# untitled.net
KiCad netlist of a schematic drawn in EAGLE
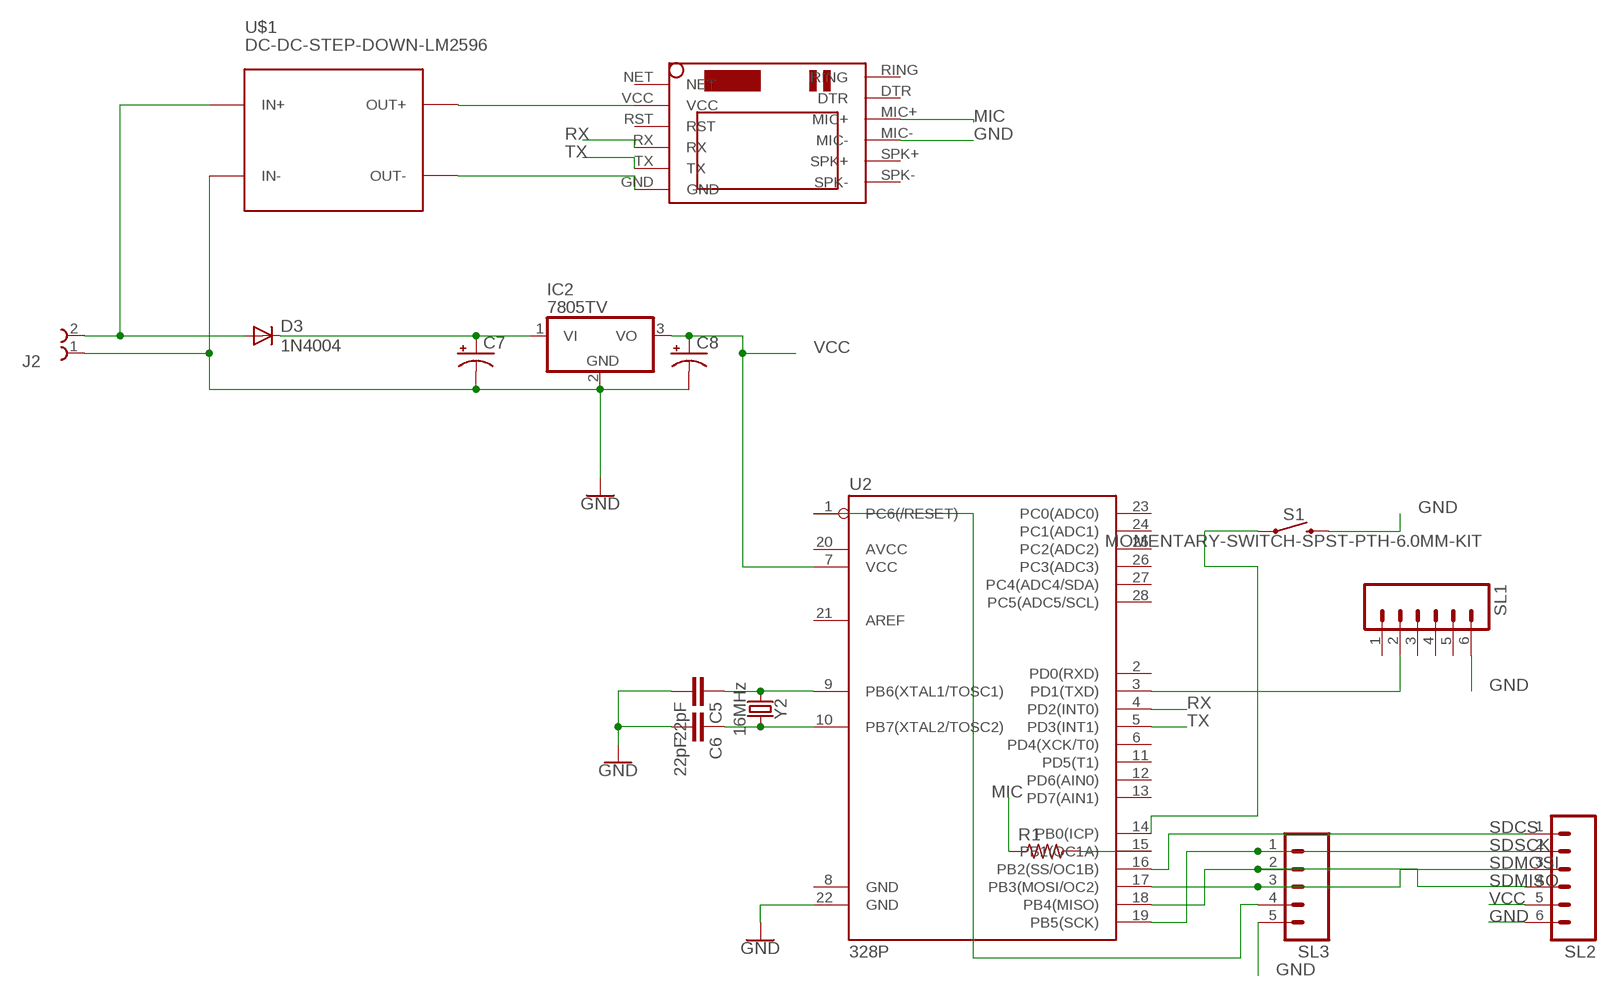
[diagram p0: schematic, sheet 1]

(export (version "E")
  (design (tool "Eeschema 10.0.6"))
  (components
    (comp (ref "C5")
      (value "22pF")
      (footprint "eagle-import:CAP-PTH-2.54")
      (libsource (lib "eagle-import") (part "22PF-PTH-2.54MM-200V-5%"))
    )
    (comp (ref "C6")
      (value "22pF")
      (footprint "eagle-import:CAP-PTH-2.54")
      (libsource (lib "eagle-import") (part "22PF-PTH-2.54MM-200V-5%"))
    )
    (comp (ref "C7")
      (value "CAPACITOR-PE5-8.5")
      (footprint "eagle-import:E5-8,5")
      (libsource (lib "eagle-import") (part "CAPACITOR-PE5-8.5"))
    )
    (comp (ref "C8")
      (value "CAPACITOR-PE5-5")
      (footprint "eagle-import:E5-5")
      (libsource (lib "eagle-import") (part "CAPACITOR-PE5-5"))
    )
    (comp (ref "D3")
      (value "1N4004")
      (footprint "eagle-import:DO41-10")
      (libsource (lib "eagle-import") (part "1N4004"))
    )
    (comp (ref "IC2")
      (value "7805TV")
      (footprint "eagle-import:TO220V")
      (libsource (lib "eagle-import") (part "78TV05"))
    )
    (comp (ref "J2")
      (value "691201520002")
      (footprint "eagle-import:691201520002")
      (libsource (lib "eagle-import") (part "691201520002"))
    )
    (comp (ref "R1")
      (value "R-US_0207/10")
      (footprint "eagle-import:0207_10")
      (libsource (lib "eagle-import") (part "R-US_0207/10"))
    )
    (comp (ref "S1")
      (value "MOMENTARY-SWITCH-SPST-PTH-6.0MM-KIT")
      (footprint "eagle-import:TACTILE_SWITCH_PTH_6.0MM_KIT")
      (libsource (lib "eagle-import") (part "MOMENTARY-SWITCH-SPST-PTH-6.0MM-KIT"))
    )
    (comp (ref "SL1")
      (value "M06")
      (footprint "eagle-import:06P")
      (libsource (lib "eagle-import") (part "M06"))
    )
    (comp (ref "SL2")
      (value "M06")
      (footprint "eagle-import:06P")
      (libsource (lib "eagle-import") (part "M06"))
    )
    (comp (ref "SL3")
      (value "M05")
      (footprint "eagle-import:05P")
      (libsource (lib "eagle-import") (part "M05"))
    )
    (comp (ref "U$1")
      (value "DC-DC-STEP-DOWN-LM2596")
      (footprint "eagle-import:DC-DC-STEP-DOWN-LM2596")
      (libsource (lib "eagle-import") (part "DC-DC-STEP-DOWN-LM2596"))
    )
    (comp (ref "U$2")
      (value "SIM800LMODULE")
      (footprint "eagle-import:SIM800LMODULE")
      (libsource (lib "eagle-import") (part "SIM800LMODULE"))
    )
    (comp (ref "U2")
      (value "328P")
      (footprint "eagle-import:DIP28")
      (libsource (lib "eagle-import") (part "ATMEGA328P_PDIP"))
    )
    (comp (ref "Y2")
      (value "16MHz")
      (footprint "eagle-import:HC49US")
      (libsource (lib "eagle-import") (part "CRYSTAL-16MHZPTH-HC49US"))
    )
  )
  (nets
    (net (code "1") (name "/MIC") (class "Default")
      (node (ref "R1") (pin "1") (pinfunction "1_1") (pintype "passive"))
      (node (ref "U$2") (pin "MIC+") (pinfunction "MIC+_MIC+") (pintype "bidirectional"))
    )
    (net (code "2") (name "/RX") (class "Default")
      (node (ref "U$2") (pin "RX") (pinfunction "RX_RX") (pintype "bidirectional"))
      (node (ref "U2") (pin "4") (pinfunction "PD2(INT0)_4") (pintype "bidirectional"))
    )
    (net (code "3") (name "/SDCS") (class "Default")
      (node (ref "SL2") (pin "1") (pinfunction "1_1") (pintype "passive"))
      (node (ref "U2") (pin "16") (pinfunction "PB2(SS/OC1B)_16") (pintype "bidirectional"))
    )
    (net (code "4") (name "/SDMISO") (class "Default")
      (node (ref "SL2") (pin "4") (pinfunction "4_4") (pintype "passive"))
      (node (ref "SL3") (pin "2") (pinfunction "2_2") (pintype "passive"))
      (node (ref "U2") (pin "18") (pinfunction "PB4(MISO)_18") (pintype "bidirectional"))
    )
    (net (code "5") (name "/SDMOSI") (class "Default")
      (node (ref "SL2") (pin "3") (pinfunction "3_3") (pintype "passive"))
      (node (ref "SL3") (pin "3") (pinfunction "3_3") (pintype "passive"))
      (node (ref "U2") (pin "17") (pinfunction "PB3(MOSI/OC2)_17") (pintype "bidirectional"))
    )
    (net (code "6") (name "/SDSCK") (class "Default")
      (node (ref "SL2") (pin "2") (pinfunction "2_2") (pintype "passive"))
      (node (ref "SL3") (pin "1") (pinfunction "1_1") (pintype "passive"))
      (node (ref "U2") (pin "19") (pinfunction "PB5(SCK)_19") (pintype "bidirectional"))
    )
    (net (code "7") (name "/TX") (class "Default")
      (node (ref "U$2") (pin "TX") (pinfunction "TX_TX") (pintype "bidirectional"))
      (node (ref "U2") (pin "5") (pinfunction "PD3(INT1)_5") (pintype "bidirectional"))
    )
    (net (code "8") (name "/VCC") (class "Default")
      (node (ref "C8") (pin "+") (pinfunction "+_+") (pintype "passive"))
      (node (ref "IC2") (pin "3") (pinfunction "VO_3") (pintype "passive"))
      (node (ref "SL2") (pin "5") (pinfunction "5_5") (pintype "passive"))
      (node (ref "U2") (pin "7") (pinfunction "VCC_7") (pintype "bidirectional"))
    )
    (net (code "9") (name "GND") (class "Default")
      (node (ref "C5") (pin "2") (pinfunction "2_2") (pintype "passive"))
      (node (ref "C6") (pin "2") (pinfunction "2_2") (pintype "passive"))
      (node (ref "C7") (pin "-") (pinfunction "-_-") (pintype "passive"))
      (node (ref "C8") (pin "-") (pinfunction "-_-") (pintype "passive"))
      (node (ref "IC2") (pin "2") (pinfunction "GND_2") (pintype "passive"))
      (node (ref "J2") (pin "1") (pinfunction "1_1") (pintype "passive"))
      (node (ref "S1") (pin "3") (pinfunction "2_3") (pintype "passive"))
      (node (ref "SL1") (pin "6") (pinfunction "6_6") (pintype "passive"))
      (node (ref "SL2") (pin "6") (pinfunction "6_6") (pintype "passive"))
      (node (ref "SL3") (pin "5") (pinfunction "5_5") (pintype "passive"))
      (node (ref "U$1") (pin "IN-") (pinfunction "IN-_IN-") (pintype "bidirectional"))
      (node (ref "U$2") (pin "MIC-") (pinfunction "MIC-_MIC-") (pintype "bidirectional"))
      (node (ref "U2") (pin "22") (pinfunction "GND_22") (pintype "bidirectional"))
    )
    (net (code "10") (name "Net-(D3-PadA)") (class "Default")
      (node (ref "D3") (pin "A") (pinfunction "A_A") (pintype "passive"))
      (node (ref "J2") (pin "2") (pinfunction "2_2") (pintype "passive"))
      (node (ref "U$1") (pin "IN+") (pinfunction "IN+_IN+") (pintype "bidirectional"))
    )
    (net (code "11") (name "Net-(IC2-VI)") (class "Default")
      (node (ref "C7") (pin "+") (pinfunction "+_+") (pintype "passive"))
      (node (ref "D3") (pin "C") (pinfunction "C_C") (pintype "passive"))
      (node (ref "IC2") (pin "1") (pinfunction "VI_1") (pintype "input"))
    )
    (net (code "12") (name "Net-(U$1-PadOUT+)") (class "Default")
      (node (ref "U$1") (pin "OUT+") (pinfunction "OUT+_OUT+") (pintype "bidirectional"))
      (node (ref "U$2") (pin "VCC") (pinfunction "VCC_VCC") (pintype "bidirectional"))
    )
    (net (code "13") (name "Net-(U$1-PadOUT-)") (class "Default")
      (node (ref "U$1") (pin "OUT-") (pinfunction "OUT-_OUT-") (pintype "bidirectional"))
      (node (ref "U$2") (pin "GND") (pinfunction "GND_GND") (pintype "bidirectional"))
    )
    (net (code "14") (name "Net-(U2-PB0(ICP))") (class "Default")
      (node (ref "S1") (pin "1") (pinfunction "1_1") (pintype "passive"))
      (node (ref "U2") (pin "14") (pinfunction "PB0(ICP)_14") (pintype "bidirectional"))
    )
    (net (code "15") (name "Net-(U2-PB1(OC1A))") (class "Default")
      (node (ref "R1") (pin "2") (pinfunction "2_2") (pintype "passive"))
      (node (ref "U2") (pin "15") (pinfunction "PB1(OC1A)_15") (pintype "bidirectional"))
    )
    (net (code "16") (name "Net-(U2-PB6(XTAL1{slash}TOSC1))") (class "Default")
      (node (ref "C5") (pin "1") (pinfunction "1_1") (pintype "passive"))
      (node (ref "U2") (pin "9") (pinfunction "PB6(XTAL1/TOSC1)_9") (pintype "bidirectional"))
      (node (ref "Y2") (pin "1") (pinfunction "1_1") (pintype "passive"))
    )
    (net (code "17") (name "Net-(U2-PB7(XTAL2{slash}TOSC2))") (class "Default")
      (node (ref "C6") (pin "1") (pinfunction "1_1") (pintype "passive"))
      (node (ref "U2") (pin "10") (pinfunction "PB7(XTAL2/TOSC2)_10") (pintype "bidirectional"))
      (node (ref "Y2") (pin "2") (pinfunction "2_2") (pintype "passive"))
    )
    (net (code "18") (name "Net-(U2-PC6({slash}RESET))") (class "Default")
      (node (ref "SL3") (pin "4") (pinfunction "4_4") (pintype "passive"))
      (node (ref "U2") (pin "1") (pinfunction "PC6(/RESET)_1") (pintype "bidirectional"))
    )
    (net (code "19") (name "Net-(U2-PD1(TXD))") (class "Default")
      (node (ref "SL1") (pin "2") (pinfunction "2_2") (pintype "passive"))
      (node (ref "U2") (pin "3") (pinfunction "PD1(TXD)_3") (pintype "bidirectional"))
    )
    (net (code "20") (name "unconnected-(SL1-Pad1)") (class "Default")
      (node (ref "SL1") (pin "1") (pinfunction "1_1") (pintype "passive"))
    )
    (net (code "21") (name "unconnected-(SL1-Pad3)") (class "Default")
      (node (ref "SL1") (pin "3") (pinfunction "3_3") (pintype "passive"))
    )
    (net (code "22") (name "unconnected-(SL1-Pad4)") (class "Default")
      (node (ref "SL1") (pin "4") (pinfunction "4_4") (pintype "passive"))
    )
    (net (code "23") (name "unconnected-(SL1-Pad5)") (class "Default")
      (node (ref "SL1") (pin "5") (pinfunction "5_5") (pintype "passive"))
    )
    (net (code "24") (name "unconnected-(U$2-PadDTR)") (class "Default")
      (node (ref "U$2") (pin "DTR") (pinfunction "DTR_DTR") (pintype "bidirectional"))
    )
    (net (code "25") (name "unconnected-(U$2-PadNET)") (class "Default")
      (node (ref "U$2") (pin "NET") (pinfunction "NET_NET") (pintype "bidirectional"))
    )
    (net (code "26") (name "unconnected-(U$2-PadRING)") (class "Default")
      (node (ref "U$2") (pin "RING") (pinfunction "RING_RING") (pintype "bidirectional"))
    )
    (net (code "27") (name "unconnected-(U$2-PadRST)") (class "Default")
      (node (ref "U$2") (pin "RST") (pinfunction "RST_RST") (pintype "bidirectional"))
    )
    (net (code "28") (name "unconnected-(U$2-PadSPK+)") (class "Default")
      (node (ref "U$2") (pin "SPK+") (pinfunction "SPK+_SPK+") (pintype "bidirectional"))
    )
    (net (code "29") (name "unconnected-(U$2-PadSPK-)") (class "Default")
      (node (ref "U$2") (pin "SPK-") (pinfunction "SPK-_SPK-") (pintype "bidirectional"))
    )
    (net (code "30") (name "unconnected-(U2-AREF-Pad21)") (class "Default")
      (node (ref "U2") (pin "21") (pinfunction "AREF_21") (pintype "bidirectional"))
    )
    (net (code "31") (name "unconnected-(U2-AVCC-Pad20)") (class "Default")
      (node (ref "U2") (pin "20") (pinfunction "AVCC_20") (pintype "bidirectional"))
    )
    (net (code "32") (name "unconnected-(U2-GND-Pad8)") (class "Default")
      (node (ref "U2") (pin "8") (pinfunction "GND_8") (pintype "bidirectional"))
    )
    (net (code "33") (name "unconnected-(U2-PC0(ADC0)-Pad23)") (class "Default")
      (node (ref "U2") (pin "23") (pinfunction "PC0(ADC0)_23") (pintype "bidirectional"))
    )
    (net (code "34") (name "unconnected-(U2-PC1(ADC1)-Pad24)") (class "Default")
      (node (ref "U2") (pin "24") (pinfunction "PC1(ADC1)_24") (pintype "bidirectional"))
    )
    (net (code "35") (name "unconnected-(U2-PC2(ADC2)-Pad25)") (class "Default")
      (node (ref "U2") (pin "25") (pinfunction "PC2(ADC2)_25") (pintype "bidirectional"))
    )
    (net (code "36") (name "unconnected-(U2-PC3(ADC3)-Pad26)") (class "Default")
      (node (ref "U2") (pin "26") (pinfunction "PC3(ADC3)_26") (pintype "bidirectional"))
    )
    (net (code "37") (name "unconnected-(U2-PC4(ADC4{slash}SDA)-Pad27)") (class "Default")
      (node (ref "U2") (pin "27") (pinfunction "PC4(ADC4/SDA)_27") (pintype "bidirectional"))
    )
    (net (code "38") (name "unconnected-(U2-PC5(ADC5{slash}SCL)-Pad28)") (class "Default")
      (node (ref "U2") (pin "28") (pinfunction "PC5(ADC5/SCL)_28") (pintype "bidirectional"))
    )
    (net (code "39") (name "unconnected-(U2-PD0(RXD)-Pad2)") (class "Default")
      (node (ref "U2") (pin "2") (pinfunction "PD0(RXD)_2") (pintype "bidirectional"))
    )
    (net (code "40") (name "unconnected-(U2-PD4(XCK{slash}T0)-Pad6)") (class "Default")
      (node (ref "U2") (pin "6") (pinfunction "PD4(XCK/T0)_6") (pintype "bidirectional"))
    )
    (net (code "41") (name "unconnected-(U2-PD5(T1)-Pad11)") (class "Default")
      (node (ref "U2") (pin "11") (pinfunction "PD5(T1)_11") (pintype "bidirectional"))
    )
    (net (code "42") (name "unconnected-(U2-PD6(AIN0)-Pad12)") (class "Default")
      (node (ref "U2") (pin "12") (pinfunction "PD6(AIN0)_12") (pintype "bidirectional"))
    )
    (net (code "43") (name "unconnected-(U2-PD7(AIN1)-Pad13)") (class "Default")
      (node (ref "U2") (pin "13") (pinfunction "PD7(AIN1)_13") (pintype "bidirectional"))
    )
  )
)
